# X-LINK-A_V2_0.net
KiCad netlist of a schematic drawn in Altium Designer
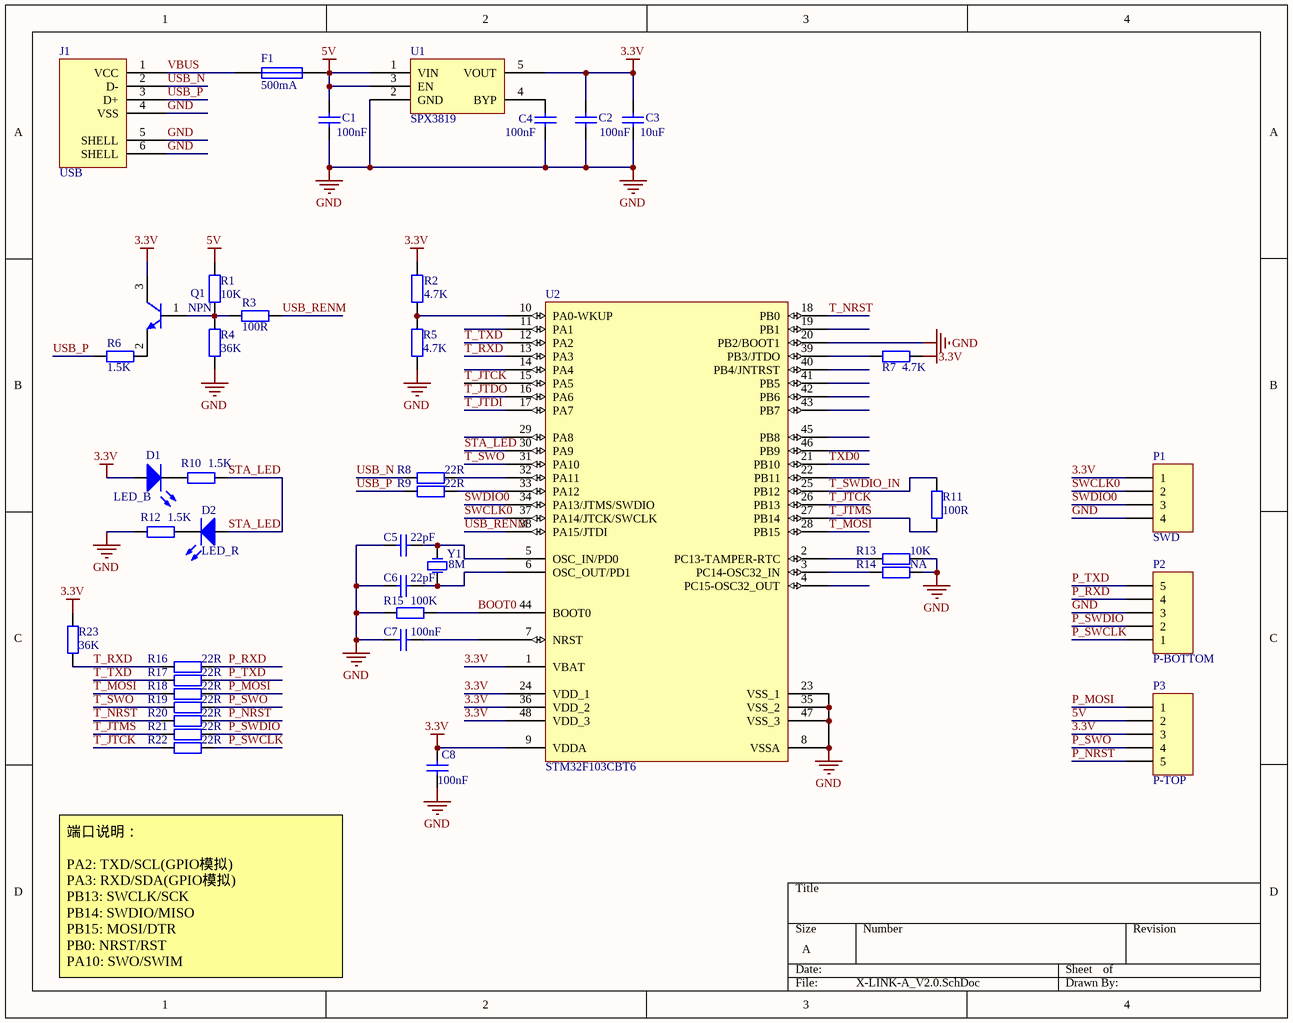
[diagram p0: X-LINK-A_V2.0.SchDoc]

(export (version "E")
  (design (tool "Eeschema 10.0.6"))
  (components
    (comp (ref "C1")
      (value "Cap")
      (footprint "C-0603")
      (description "Capacitor")
      (fields (field (name "CAP") "100nF") (field (name "PUBLISHER") "Altium Limited"))
      (libsource (lib "Miscellaneous Devices") (part "Cap"))
    )
    (comp (ref "C2")
      (value "Cap")
      (footprint "C-0603")
      (description "Capacitor")
      (fields (field (name "CAP") "100nF") (field (name "PUBLISHER") "Altium Limited"))
      (libsource (lib "Miscellaneous Devices") (part "Cap"))
    )
    (comp (ref "C3")
      (value "Cap")
      (footprint "C-0603")
      (description "Capacitor")
      (fields (field (name "CAP") "10uF") (field (name "PUBLISHER") "Altium Limited"))
      (libsource (lib "Miscellaneous Devices") (part "Cap"))
    )
    (comp (ref "C4")
      (value "Cap")
      (footprint "C-0603")
      (description "Capacitor")
      (fields (field (name "CAP") "100nF") (field (name "PUBLISHER") "Altium Limited"))
      (libsource (lib "Miscellaneous Devices") (part "Cap"))
    )
    (comp (ref "C5")
      (value "Cap")
      (footprint "C-0603")
      (fields (field (name "CAP") "22pF"))
      (libsource (lib "WK_PCB") (part "Cap"))
    )
    (comp (ref "C6")
      (value "Cap")
      (footprint "C-0603")
      (fields (field (name "CAP") "22pF"))
      (libsource (lib "WK_PCB") (part "Cap"))
    )
    (comp (ref "C7")
      (value "Cap")
      (footprint "C-0603")
      (fields (field (name "CAP") "100nF"))
      (libsource (lib "WK_PCB") (part "Cap"))
    )
    (comp (ref "C8")
      (value "Cap")
      (footprint "C-0603")
      (description "Capacitor")
      (fields (field (name "CAP") "100nF") (field (name "PUBLISHER") "Altium Limited"))
      (libsource (lib "Miscellaneous Devices") (part "Cap"))
    )
    (comp (ref "D1")
      (value "LED_B")
      (footprint "SMT_LED_0603")
      (description "Typical RED, GREEN, YELLOW, AMBER GaAs LED")
      (fields (field (name "PUBLISHER") "Altium Limited"))
      (libsource (lib "ST-Link-V2.2") (part "LED2"))
    )
    (comp (ref "D2")
      (value "LED_R")
      (footprint "SMT_LED_0603")
      (description "Typical RED, GREEN, YELLOW, AMBER GaAs LED")
      (fields (field (name "PUBLISHER") "Altium Limited"))
      (libsource (lib "ST-Link-V2.2") (part "LED2"))
    )
    (comp (ref "F1")
      (value "Fuse1")
      (footprint "0805-1")
      (description "保险丝")
      (fields (field (name "FUSE") "500mA"))
      (libsource (lib "ST-Link-V2.2") (part "Fuse1"))
    )
    (comp (ref "J1")
      (value "USB")
      (footprint "USB-B")
      (description "USB接口")
      (libsource (lib "HDR_Fszhang") (part "USB"))
    )
    (comp (ref "P1")
      (value "SWD")
      (footprint "SIP4-1.27")
      (description "Header, 4-Pin")
      (fields (field (name "PUBLISHER") "Altium Limited"))
      (libsource (lib "Miscellaneous Connectors") (part "Header 4"))
    )
    (comp (ref "P2")
      (value "P-BOTTOM")
      (footprint "HEADER_5")
      (description "Header, 5-Pin")
      (fields (field (name "PUBLISHER") "Altium Limited"))
      (libsource (lib "Miscellaneous Connectors") (part "Header 5"))
    )
    (comp (ref "P3")
      (value "P-TOP")
      (footprint "HEADER_5")
      (description "Header, 5-Pin")
      (fields (field (name "PUBLISHER") "Altium Limited"))
      (libsource (lib "") (part "Header 5_1"))
    )
    (comp (ref "Q1")
      (value "NPN")
      (footprint "SOT23-3")
      (description "贴片三极管")
      (fields (field (name "PUBLISHER") "Altium Limited"))
      (libsource (lib "Fszhang") (part "NPN1"))
    )
    (comp (ref "R1")
      (value "Res1")
      (footprint "0603-1")
      (description "贴片电阻")
      (fields (field (name "RES") "10K") (field (name "PUBLISHER") "Altium Limited"))
      (libsource (lib "") (part "Res1_2"))
    )
    (comp (ref "R2")
      (value "Res2")
      (footprint "0603-1")
      (description "Resistor")
      (fields (field (name "RES") "4.7K") (field (name "PUBLISHER") "Altium Limited"))
      (libsource (lib "") (part "Res2_1"))
    )
    (comp (ref "R3")
      (value "Res1")
      (footprint "0603-1")
      (description "贴片电阻")
      (fields (field (name "RES") "100R") (field (name "PUBLISHER") "Altium Limited"))
      (libsource (lib "Fszhang") (part "Res1"))
    )
    (comp (ref "R4")
      (value "Res1")
      (footprint "0603-1")
      (description "贴片电阻")
      (fields (field (name "RES") "36K") (field (name "PUBLISHER") "Altium Limited"))
      (libsource (lib "") (part "Res1_2"))
    )
    (comp (ref "R5")
      (value "Res2")
      (footprint "0603-1")
      (description "Resistor")
      (fields (field (name "RES") "4.7K") (field (name "PUBLISHER") "Altium Limited"))
      (libsource (lib "") (part "Res2_1"))
    )
    (comp (ref "R6")
      (value "Res1")
      (footprint "0603-1")
      (description "贴片电阻")
      (fields (field (name "RES") "1.5K") (field (name "PUBLISHER") "Altium Limited"))
      (libsource (lib "") (part "Res1_1"))
    )
    (comp (ref "R7")
      (value "Res2")
      (footprint "0603-1")
      (description "Resistor")
      (fields (field (name "RES") "4.7K") (field (name "PUBLISHER") "Altium Limited"))
      (libsource (lib "Miscellaneous Devices") (part "Res2"))
    )
    (comp (ref "R8")
      (value "Res2")
      (footprint "0603-1")
      (description "Resistor")
      (fields (field (name "RES") "22R") (field (name "PUBLISHER") "Altium Limited"))
      (libsource (lib "Miscellaneous Devices") (part "Res2"))
    )
    (comp (ref "R9")
      (value "Res2")
      (footprint "0603-1")
      (description "Resistor")
      (fields (field (name "RES") "22R") (field (name "PUBLISHER") "Altium Limited"))
      (libsource (lib "Miscellaneous Devices") (part "Res2"))
    )
    (comp (ref "R10")
      (value "Res2")
      (footprint "0603-1")
      (description "Resistor")
      (fields (field (name "RES") "1.5K") (field (name "PUBLISHER") "Altium Limited"))
      (libsource (lib "Miscellaneous Devices") (part "Res2"))
    )
    (comp (ref "R11")
      (value "Res2")
      (footprint "0603-1")
      (description "Resistor")
      (fields (field (name "RES") "100R") (field (name "PUBLISHER") "Altium Limited"))
      (libsource (lib "") (part "Res2_1"))
    )
    (comp (ref "R12")
      (value "1.5K")
      (footprint "0603-1")
      (description "Resistor")
      (fields (field (name "Comment") "Res2") (field (name "PUBLISHER") "Altium Limited"))
      (libsource (lib "") (part "Res2_1"))
    )
    (comp (ref "R13")
      (value "Res1")
      (footprint "0603-1")
      (description "贴片电阻")
      (fields (field (name "RES") "10K") (field (name "PUBLISHER") "Altium Limited"))
      (libsource (lib "Fszhang") (part "Res1"))
    )
    (comp (ref "R14")
      (value "Res1")
      (footprint "0603-1")
      (description "贴片电阻")
      (fields (field (name "RES") "NA") (field (name "PUBLISHER") "Altium Limited"))
      (libsource (lib "Fszhang") (part "Res1"))
    )
    (comp (ref "R15")
      (value "Res2")
      (footprint "0603-1")
      (description "Resistor")
      (fields (field (name "RES") "100K") (field (name "PUBLISHER") "Altium Limited"))
      (libsource (lib "Miscellaneous Devices") (part "Res2"))
    )
    (comp (ref "R16")
      (value "Res2")
      (footprint "0603-1")
      (description "Resistor")
      (fields (field (name "RES") "22R") (field (name "PUBLISHER") "Altium Limited"))
      (libsource (lib "Miscellaneous Devices") (part "Res2"))
    )
    (comp (ref "R17")
      (value "Res2")
      (footprint "0603-1")
      (description "Resistor")
      (fields (field (name "RES") "22R") (field (name "PUBLISHER") "Altium Limited"))
      (libsource (lib "Miscellaneous Devices") (part "Res2"))
    )
    (comp (ref "R18")
      (value "Res2")
      (footprint "0603-1")
      (description "Resistor")
      (fields (field (name "RES") "22R") (field (name "PUBLISHER") "Altium Limited"))
      (libsource (lib "Miscellaneous Devices") (part "Res2"))
    )
    (comp (ref "R19")
      (value "Res2")
      (footprint "0603-1")
      (description "Resistor")
      (fields (field (name "RES") "22R") (field (name "PUBLISHER") "Altium Limited"))
      (libsource (lib "Miscellaneous Devices") (part "Res2"))
    )
    (comp (ref "R20")
      (value "Res2")
      (footprint "0603-1")
      (description "Resistor")
      (fields (field (name "RES") "22R") (field (name "PUBLISHER") "Altium Limited"))
      (libsource (lib "Miscellaneous Devices") (part "Res2"))
    )
    (comp (ref "R21")
      (value "Res2")
      (footprint "0603-1")
      (description "Resistor")
      (fields (field (name "RES") "22R") (field (name "PUBLISHER") "Altium Limited"))
      (libsource (lib "Miscellaneous Devices") (part "Res2"))
    )
    (comp (ref "R22")
      (value "Res2")
      (footprint "0603-1")
      (description "Resistor")
      (fields (field (name "RES") "22R") (field (name "PUBLISHER") "Altium Limited"))
      (libsource (lib "Miscellaneous Devices") (part "Res2"))
    )
    (comp (ref "R23")
      (value "Res1")
      (footprint "0603-1")
      (description "贴片电阻")
      (fields (field (name "RES") "36K") (field (name "PUBLISHER") "Altium Limited"))
      (libsource (lib "") (part "Res1_2"))
    )
    (comp (ref "U1") (value "SPX3819") (footprint "SOT23-5") (libsource (lib "Schlib1") (part "SPX3819")))
    (comp (ref "U2")
      (value "STM32F103CBT6")
      (footprint "LQFP48_N")
      (description "STM32 ARM-based 32-bit MCU with 64 Kbytes Flash, 48-pin LQFP, Industrial Temperature")
      (fields (field (name "PUBLISHER") "Altium Limited"))
      (libsource (lib "ST Microcontroller 32-Bit STM32") (part "STM32F103C8T6"))
    )
    (comp (ref "Y1")
      (value "8M")
      (footprint "XAL5032 2-Leads")
      (description "Crystal Oscillator")
      (fields
        (field (name "MANUFACTURER") "Generic Components")
        (field (name "PUBLISHER") "Altium Hobart Technology Centre")
      )
      (libsource (lib "*") (part "XTAL"))
    )
  )
  (nets
    (net (code "1") (name "/BOOT0") (class "Default")
      (node (ref "R15") (pin "2") (pinfunction "2_2") (pintype "passive"))
      (node (ref "U2") (pin "44") (pinfunction "BOOT0_44") (pintype "passive"))
    )
    (net (code "2") (name "/P_MOSI") (class "Default")
      (node (ref "P3") (pin "1") (pinfunction "1_1") (pintype "passive"))
      (node (ref "R18") (pin "2") (pinfunction "2_2") (pintype "passive"))
    )
    (net (code "3") (name "/P_NRST") (class "Default")
      (node (ref "P3") (pin "5") (pinfunction "5_5") (pintype "passive"))
      (node (ref "R20") (pin "2") (pinfunction "2_2") (pintype "passive"))
    )
    (net (code "4") (name "/P_RXD") (class "Default")
      (node (ref "P2") (pin "4") (pinfunction "4_4") (pintype "passive"))
      (node (ref "R16") (pin "2") (pinfunction "2_2") (pintype "passive"))
    )
    (net (code "5") (name "/P_SWCLK") (class "Default")
      (node (ref "P2") (pin "1") (pinfunction "1_1") (pintype "passive"))
      (node (ref "R22") (pin "2") (pinfunction "2_2") (pintype "passive"))
    )
    (net (code "6") (name "/P_SWDIO") (class "Default")
      (node (ref "P2") (pin "2") (pinfunction "2_2") (pintype "passive"))
      (node (ref "R21") (pin "2") (pinfunction "2_2") (pintype "passive"))
    )
    (net (code "7") (name "/P_SWO") (class "Default")
      (node (ref "P3") (pin "4") (pinfunction "4_4") (pintype "passive"))
      (node (ref "R19") (pin "2") (pinfunction "2_2") (pintype "passive"))
    )
    (net (code "8") (name "/P_TXD") (class "Default")
      (node (ref "P2") (pin "5") (pinfunction "5_5") (pintype "passive"))
      (node (ref "R17") (pin "2") (pinfunction "2_2") (pintype "passive"))
    )
    (net (code "9") (name "/STA_LED") (class "Default")
      (node (ref "D2") (pin "1") (pinfunction "A_1") (pintype "passive"))
      (node (ref "R10") (pin "2") (pinfunction "2_2") (pintype "passive"))
      (node (ref "U2") (pin "30") (pinfunction "PA9_30") (pintype "bidirectional"))
    )
    (net (code "10") (name "/SWCLK0") (class "Default")
      (node (ref "P1") (pin "2") (pinfunction "2_2") (pintype "passive"))
      (node (ref "U2") (pin "37") (pinfunction "PA14/JTCK/SWCLK_37") (pintype "bidirectional"))
    )
    (net (code "11") (name "/SWDIO0") (class "Default")
      (node (ref "P1") (pin "3") (pinfunction "3_3") (pintype "passive"))
      (node (ref "U2") (pin "34") (pinfunction "PA13/JTMS/SWDIO_34") (pintype "bidirectional"))
    )
    (net (code "12") (name "/TXD0") (class "Default")
      (node (ref "U2") (pin "21") (pinfunction "PB10_21") (pintype "bidirectional"))
    )
    (net (code "13") (name "/T_JTCK") (class "Default")
      (node (ref "R22") (pin "1") (pinfunction "1_1") (pintype "passive"))
      (node (ref "U2") (pin "15") (pinfunction "PA5_15") (pintype "bidirectional"))
      (node (ref "U2") (pin "26") (pinfunction "PB13_26") (pintype "bidirectional"))
    )
    (net (code "14") (name "/T_JTDI") (class "Default")
      (node (ref "U2") (pin "17") (pinfunction "PA7_17") (pintype "bidirectional"))
    )
    (net (code "15") (name "/T_JTDO") (class "Default")
      (node (ref "U2") (pin "16") (pinfunction "PA6_16") (pintype "bidirectional"))
    )
    (net (code "16") (name "/T_JTMS") (class "Default")
      (node (ref "R11") (pin "1") (pinfunction "1_1") (pintype "passive"))
      (node (ref "R21") (pin "1") (pinfunction "1_1") (pintype "passive"))
      (node (ref "U2") (pin "27") (pinfunction "PB14_27") (pintype "bidirectional"))
    )
    (net (code "17") (name "/T_MOSI") (class "Default")
      (node (ref "R18") (pin "1") (pinfunction "1_1") (pintype "passive"))
      (node (ref "U2") (pin "28") (pinfunction "PB15_28") (pintype "bidirectional"))
    )
    (net (code "18") (name "/T_NRST") (class "Default")
      (node (ref "R20") (pin "1") (pinfunction "1_1") (pintype "passive"))
      (node (ref "U2") (pin "18") (pinfunction "PB0_18") (pintype "bidirectional"))
    )
    (net (code "19") (name "/T_RXD") (class "Default")
      (node (ref "R16") (pin "1") (pinfunction "1_1") (pintype "passive"))
      (node (ref "R23") (pin "2") (pinfunction "2_2") (pintype "passive"))
      (node (ref "U2") (pin "13") (pinfunction "PA3_13") (pintype "bidirectional"))
    )
    (net (code "20") (name "/T_SWDIO_IN") (class "Default")
      (node (ref "R11") (pin "2") (pinfunction "2_2") (pintype "passive"))
      (node (ref "U2") (pin "25") (pinfunction "PB12_25") (pintype "bidirectional"))
    )
    (net (code "21") (name "/T_SWO") (class "Default")
      (node (ref "R19") (pin "1") (pinfunction "1_1") (pintype "passive"))
      (node (ref "U2") (pin "31") (pinfunction "PA10_31") (pintype "bidirectional"))
    )
    (net (code "22") (name "/T_TXD") (class "Default")
      (node (ref "R17") (pin "1") (pinfunction "1_1") (pintype "passive"))
      (node (ref "U2") (pin "12") (pinfunction "PA2_12") (pintype "bidirectional"))
    )
    (net (code "23") (name "/USB_N") (class "Default")
      (node (ref "J1") (pin "2") (pinfunction "D-_2") (pintype "passive"))
      (node (ref "R8") (pin "1") (pinfunction "1_1") (pintype "passive"))
    )
    (net (code "24") (name "/USB_P") (class "Default")
      (node (ref "J1") (pin "3") (pinfunction "D+_3") (pintype "passive"))
      (node (ref "R6") (pin "2") (pinfunction "2_2") (pintype "passive"))
      (node (ref "R9") (pin "1") (pinfunction "1_1") (pintype "passive"))
    )
    (net (code "25") (name "/USB_RENM") (class "Default")
      (node (ref "R3") (pin "2") (pinfunction "2_2") (pintype "passive"))
      (node (ref "U2") (pin "38") (pinfunction "PA15/JTDI_38") (pintype "bidirectional"))
    )
    (net (code "26") (name "/VBUS") (class "Default")
      (node (ref "F1") (pin "1") (pinfunction "1_1") (pintype "passive"))
      (node (ref "J1") (pin "1") (pinfunction "VCC_1") (pintype "passive"))
    )
    (net (code "27") (name "3.3V") (class "Default")
      (node (ref "C2") (pin "2") (pinfunction "2_2") (pintype "passive"))
      (node (ref "C3") (pin "2") (pinfunction "2_2") (pintype "passive"))
      (node (ref "C8") (pin "2") (pinfunction "2_2") (pintype "passive"))
      (node (ref "D1") (pin "1") (pinfunction "A_1") (pintype "passive"))
      (node (ref "P1") (pin "1") (pinfunction "1_1") (pintype "passive"))
      (node (ref "P3") (pin "3") (pinfunction "3_3") (pintype "passive"))
      (node (ref "Q1") (pin "3") (pinfunction "C_3") (pintype "passive"))
      (node (ref "R2") (pin "2") (pinfunction "2_2") (pintype "passive"))
      (node (ref "R23") (pin "1") (pinfunction "1_1") (pintype "passive"))
      (node (ref "R7") (pin "2") (pinfunction "2_2") (pintype "passive"))
      (node (ref "U1") (pin "5") (pinfunction "VOUT_5") (pintype "passive"))
      (node (ref "U2") (pin "1") (pinfunction "VBAT_1") (pintype "power_in"))
      (node (ref "U2") (pin "24") (pinfunction "VDD_1_24") (pintype "power_in"))
      (node (ref "U2") (pin "36") (pinfunction "VDD_2_36") (pintype "power_in"))
      (node (ref "U2") (pin "48") (pinfunction "VDD_3_48") (pintype "power_in"))
      (node (ref "U2") (pin "9") (pinfunction "VDDA_9") (pintype "power_in"))
    )
    (net (code "28") (name "5V") (class "Default")
      (node (ref "C1") (pin "2") (pinfunction "2_2") (pintype "passive"))
      (node (ref "F1") (pin "2") (pinfunction "2_2") (pintype "passive"))
      (node (ref "P3") (pin "2") (pinfunction "2_2") (pintype "passive"))
      (node (ref "R1") (pin "1") (pinfunction "1_1") (pintype "passive"))
      (node (ref "U1") (pin "1") (pinfunction "VIN_1") (pintype "passive"))
      (node (ref "U1") (pin "3") (pinfunction "EN_3") (pintype "passive"))
    )
    (net (code "29") (name "GND") (class "Default")
      (node (ref "C1") (pin "1") (pinfunction "1_1") (pintype "passive"))
      (node (ref "C2") (pin "1") (pinfunction "1_1") (pintype "passive"))
      (node (ref "C3") (pin "1") (pinfunction "1_1") (pintype "passive"))
      (node (ref "C4") (pin "1") (pinfunction "1_1") (pintype "passive"))
      (node (ref "C5") (pin "1") (pinfunction "1_1") (pintype "passive"))
      (node (ref "C6") (pin "1") (pinfunction "1_1") (pintype "passive"))
      (node (ref "C7") (pin "1") (pinfunction "1_1") (pintype "passive"))
      (node (ref "C8") (pin "1") (pinfunction "1_1") (pintype "passive"))
      (node (ref "J1") (pin "4") (pinfunction "VSS_4") (pintype "passive"))
      (node (ref "J1") (pin "5") (pinfunction "SHELL_5") (pintype "passive"))
      (node (ref "J1") (pin "6") (pinfunction "SHELL_6") (pintype "passive"))
      (node (ref "P1") (pin "4") (pinfunction "4_4") (pintype "passive"))
      (node (ref "P2") (pin "3") (pinfunction "3_3") (pintype "passive"))
      (node (ref "R12") (pin "1") (pinfunction "1_1") (pintype "passive"))
      (node (ref "R13") (pin "2") (pinfunction "2_2") (pintype "passive"))
      (node (ref "R14") (pin "2") (pinfunction "2_2") (pintype "passive"))
      (node (ref "R15") (pin "1") (pinfunction "1_1") (pintype "passive"))
      (node (ref "R4") (pin "2") (pinfunction "2_2") (pintype "passive"))
      (node (ref "R5") (pin "1") (pinfunction "1_1") (pintype "passive"))
      (node (ref "U1") (pin "2") (pinfunction "GND_2") (pintype "passive"))
      (node (ref "U2") (pin "20") (pinfunction "PB2/BOOT1_20") (pintype "bidirectional"))
      (node (ref "U2") (pin "23") (pinfunction "VSS_1_23") (pintype "power_in"))
      (node (ref "U2") (pin "35") (pinfunction "VSS_2_35") (pintype "power_in"))
      (node (ref "U2") (pin "47") (pinfunction "VSS_3_47") (pintype "power_in"))
      (node (ref "U2") (pin "8") (pinfunction "VSSA_8") (pintype "power_in"))
    )
    (net (code "30") (name "Net-(D1-K)") (class "Default")
      (node (ref "D1") (pin "2") (pinfunction "K_2") (pintype "passive"))
      (node (ref "R10") (pin "1") (pinfunction "1_1") (pintype "passive"))
    )
    (net (code "31") (name "Net-(D2-K)") (class "Default")
      (node (ref "D2") (pin "2") (pinfunction "K_2") (pintype "passive"))
      (node (ref "R12") (pin "2") (pinfunction "2_2") (pintype "passive"))
    )
    (net (code "32") (name "Net-(Q1-B)") (class "Default")
      (node (ref "Q1") (pin "1") (pinfunction "B_1") (pintype "passive"))
      (node (ref "R1") (pin "2") (pinfunction "2_2") (pintype "passive"))
      (node (ref "R3") (pin "1") (pinfunction "1_1") (pintype "passive"))
      (node (ref "R4") (pin "1") (pinfunction "1_1") (pintype "passive"))
    )
    (net (code "33") (name "Net-(Q1-E)") (class "Default")
      (node (ref "Q1") (pin "2") (pinfunction "E_2") (pintype "passive"))
      (node (ref "R6") (pin "1") (pinfunction "1_1") (pintype "passive"))
    )
    (net (code "34") (name "Net-(U1-BYP)") (class "Default")
      (node (ref "C4") (pin "2") (pinfunction "2_2") (pintype "passive"))
      (node (ref "U1") (pin "4") (pinfunction "BYP_4") (pintype "passive"))
    )
    (net (code "35") (name "Net-(U2-NRST)") (class "Default")
      (node (ref "C7") (pin "2") (pinfunction "2_2") (pintype "passive"))
      (node (ref "U2") (pin "7") (pinfunction "NRST_7") (pintype "bidirectional"))
    )
    (net (code "36") (name "Net-(U2-OSC_IN{slash}PD0)") (class "Default")
      (node (ref "C5") (pin "2") (pinfunction "2_2") (pintype "passive"))
      (node (ref "U2") (pin "5") (pinfunction "OSC_IN/PD0_5") (pintype "passive"))
      (node (ref "Y1") (pin "1") (pinfunction "OSC1_1") (pintype "passive"))
    )
    (net (code "37") (name "Net-(U2-OSC_OUT{slash}PD1)") (class "Default")
      (node (ref "C6") (pin "2") (pinfunction "2_2") (pintype "passive"))
      (node (ref "U2") (pin "6") (pinfunction "OSC_OUT/PD1_6") (pintype "passive"))
      (node (ref "Y1") (pin "2") (pinfunction "OSC2_2") (pintype "passive"))
    )
    (net (code "38") (name "Net-(U2-PA0-WKUP)") (class "Default")
      (node (ref "R2") (pin "1") (pinfunction "1_1") (pintype "passive"))
      (node (ref "R5") (pin "2") (pinfunction "2_2") (pintype "passive"))
      (node (ref "U2") (pin "10") (pinfunction "PA0-WKUP_10") (pintype "bidirectional"))
    )
    (net (code "39") (name "Net-(U2-PA11)") (class "Default")
      (node (ref "R8") (pin "2") (pinfunction "2_2") (pintype "passive"))
      (node (ref "U2") (pin "32") (pinfunction "PA11_32") (pintype "bidirectional"))
    )
    (net (code "40") (name "Net-(U2-PA12)") (class "Default")
      (node (ref "R9") (pin "2") (pinfunction "2_2") (pintype "passive"))
      (node (ref "U2") (pin "33") (pinfunction "PA12_33") (pintype "bidirectional"))
    )
    (net (code "41") (name "Net-(U2-PB3{slash}JTDO)") (class "Default")
      (node (ref "R7") (pin "1") (pinfunction "1_1") (pintype "passive"))
      (node (ref "U2") (pin "39") (pinfunction "PB3/JTDO_39") (pintype "bidirectional"))
    )
    (net (code "42") (name "Net-(U2-PC13-TAMPER-RTC)") (class "Default")
      (node (ref "R13") (pin "1") (pinfunction "1_1") (pintype "passive"))
      (node (ref "U2") (pin "2") (pinfunction "PC13-TAMPER-RTC_2") (pintype "bidirectional"))
    )
    (net (code "43") (name "Net-(U2-PC14-OSC32_IN)") (class "Default")
      (node (ref "R14") (pin "1") (pinfunction "1_1") (pintype "passive"))
      (node (ref "U2") (pin "3") (pinfunction "PC14-OSC32_IN_3") (pintype "bidirectional"))
    )
    (net (code "44") (name "unconnected-(U2-PA1-Pad11)") (class "Default")
      (node (ref "U2") (pin "11") (pinfunction "PA1_11") (pintype "bidirectional"))
    )
    (net (code "45") (name "unconnected-(U2-PA4-Pad14)") (class "Default")
      (node (ref "U2") (pin "14") (pinfunction "PA4_14") (pintype "bidirectional"))
    )
    (net (code "46") (name "unconnected-(U2-PA8-Pad29)") (class "Default")
      (node (ref "U2") (pin "29") (pinfunction "PA8_29") (pintype "bidirectional"))
    )
    (net (code "47") (name "unconnected-(U2-PB1-Pad19)") (class "Default")
      (node (ref "U2") (pin "19") (pinfunction "PB1_19") (pintype "bidirectional"))
    )
    (net (code "48") (name "unconnected-(U2-PB4{slash}JNTRST-Pad40)") (class "Default")
      (node (ref "U2") (pin "40") (pinfunction "PB4/JNTRST_40") (pintype "bidirectional"))
    )
    (net (code "49") (name "unconnected-(U2-PB5-Pad41)") (class "Default")
      (node (ref "U2") (pin "41") (pinfunction "PB5_41") (pintype "bidirectional"))
    )
    (net (code "50") (name "unconnected-(U2-PB6-Pad42)") (class "Default")
      (node (ref "U2") (pin "42") (pinfunction "PB6_42") (pintype "bidirectional"))
    )
    (net (code "51") (name "unconnected-(U2-PB7-Pad43)") (class "Default")
      (node (ref "U2") (pin "43") (pinfunction "PB7_43") (pintype "bidirectional"))
    )
    (net (code "52") (name "unconnected-(U2-PB8-Pad45)") (class "Default")
      (node (ref "U2") (pin "45") (pinfunction "PB8_45") (pintype "bidirectional"))
    )
    (net (code "53") (name "unconnected-(U2-PB9-Pad46)") (class "Default")
      (node (ref "U2") (pin "46") (pinfunction "PB9_46") (pintype "bidirectional"))
    )
    (net (code "54") (name "unconnected-(U2-PB11-Pad22)") (class "Default")
      (node (ref "U2") (pin "22") (pinfunction "PB11_22") (pintype "bidirectional"))
    )
    (net (code "55") (name "unconnected-(U2-PC15-OSC32_OUT-Pad4)") (class "Default")
      (node (ref "U2") (pin "4") (pinfunction "PC15-OSC32_OUT_4") (pintype "bidirectional"))
    )
  )
)
